# PID_controller.net
KiCad netlist of a schematic drawn in Altium Designer
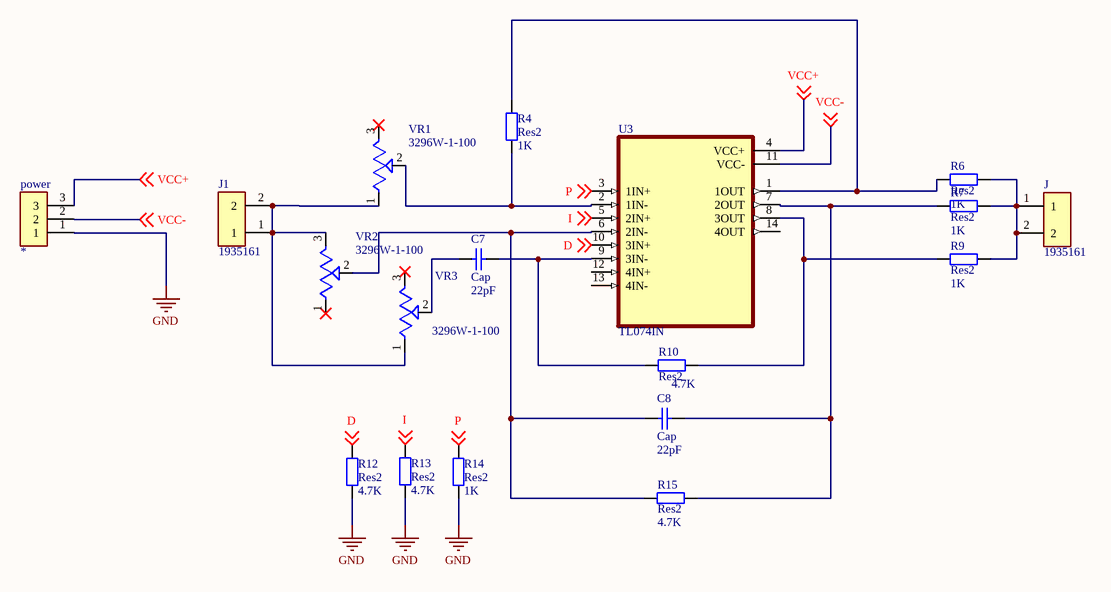
[diagram p0: PID_controller.SchDoc]

(export (version "E")
  (design (tool "Eeschema 10.0.6"))
  (components
    (comp (ref "C7")
      (value "Cap")
      (footprint "RAD-0.3")
      (description "Capacitor")
      (fields (field (name "ALTIUM_VALUE") "22pF") (field (name "PUBLISHER") "Altium Limited"))
      (libsource (lib "Miscellaneous Devices") (part "Cap"))
    )
    (comp (ref "C8")
      (value "Cap")
      (footprint "RAD-0.3")
      (description "Capacitor")
      (fields (field (name "ALTIUM_VALUE") "22pF") (field (name "PUBLISHER") "Altium Limited"))
      (libsource (lib "Miscellaneous Devices") (part "Cap"))
    )
    (comp (ref "J")
      (value "1935161")
      (footprint "PHOENIX_1935161")
      (description "2 Position Wire to Board Terminal Block Horizontal with Board 0.197 _5.00mm_ Through Hole")
      (fields (field (name "MF") "Phoenix Contact") (field (name "DIGI-KEY_PART_NUMBER") "277-1667-ND"))
      (libsource (lib "") (part "1935161_1"))
    )
    (comp (ref "J1")
      (value "1935161")
      (footprint "PHOENIX_1935161")
      (description "2 Position Wire to Board Terminal Block Horizontal with Board 0.197 _5.00mm_ Through Hole")
      (fields (field (name "MF") "Phoenix Contact") (field (name "DIGI-KEY_PART_NUMBER") "277-1667-ND"))
      (libsource (lib "1935161 (1)") (part "1935161"))
    )
    (comp (ref "power")
      (value "282837-3")
      (footprint "TE_282837-3")
      (description "Wire to Board 3 Position 5.08 mm Pitch 30-16 AWG Euro Style Terminal Block")
      (fields
        (field (name "MF") "TE Connectivity")
        (field (name "DIGI-KEY_PART_NUMBER") "A113321-ND")
        (field (name "COMMENT_1") "*")
      )
      (libsource (lib "282837-3") (part "282837-3"))
    )
    (comp (ref "R4")
      (value "Res2")
      (footprint "AXIAL-0.4")
      (description "Resistor")
      (fields (field (name "ALTIUM_VALUE") "1K") (field (name "PUBLISHER") "Altium Limited"))
      (libsource (lib "") (part "Res2_2"))
    )
    (comp (ref "R6")
      (value "Res2")
      (footprint "AXIAL-0.4")
      (description "Resistor")
      (fields (field (name "ALTIUM_VALUE") "1K") (field (name "PUBLISHER") "Altium Limited"))
      (libsource (lib "Miscellaneous Devices") (part "Res2"))
    )
    (comp (ref "R7")
      (value "Res2")
      (footprint "AXIAL-0.4")
      (description "Resistor")
      (fields (field (name "ALTIUM_VALUE") "1K") (field (name "PUBLISHER") "Altium Limited"))
      (libsource (lib "Miscellaneous Devices") (part "Res2"))
    )
    (comp (ref "R9")
      (value "Res2")
      (footprint "AXIAL-0.4")
      (description "Resistor")
      (fields (field (name "ALTIUM_VALUE") "1K") (field (name "PUBLISHER") "Altium Limited"))
      (libsource (lib "Miscellaneous Devices") (part "Res2"))
    )
    (comp (ref "R10")
      (value "Res2")
      (footprint "AXIAL-0.4")
      (description "Resistor")
      (fields (field (name "ALTIUM_VALUE") "4.7K") (field (name "PUBLISHER") "Altium Limited"))
      (libsource (lib "Miscellaneous Devices") (part "Res2"))
    )
    (comp (ref "R12")
      (value "Res2")
      (footprint "AXIAL-0.4")
      (description "Resistor")
      (fields (field (name "ALTIUM_VALUE") "4.7K") (field (name "PUBLISHER") "Altium Limited"))
      (libsource (lib "") (part "Res2_2"))
    )
    (comp (ref "R13")
      (value "Res2")
      (footprint "AXIAL-0.4")
      (description "Resistor")
      (fields (field (name "ALTIUM_VALUE") "4.7K") (field (name "PUBLISHER") "Altium Limited"))
      (libsource (lib "") (part "Res2_2"))
    )
    (comp (ref "R14")
      (value "Res2")
      (footprint "AXIAL-0.4")
      (description "Resistor")
      (fields (field (name "ALTIUM_VALUE") "1K") (field (name "PUBLISHER") "Altium Limited"))
      (libsource (lib "") (part "Res2_2"))
    )
    (comp (ref "R15")
      (value "Res2")
      (footprint "AXIAL-0.4")
      (description "Resistor")
      (fields (field (name "ALTIUM_VALUE") "4.7K") (field (name "PUBLISHER") "Altium Limited"))
      (libsource (lib "") (part "Res2_1"))
    )
    (comp (ref "U3")
      (value "TL074IN")
      (footprint "DIP794W45P254L1969H508Q14")
      (description "J-FET Amplifier 4 Circuit 14-DIP")
      (fields (field (name "MF") "STMicroelectronics"))
      (libsource (lib "TL074IN") (part "TL074IN"))
    )
    (comp (ref "VR1")
      (value "3296W-1-100")
      (footprint "TRIM_3296W-1-100")
      (description "10 Ohms 0.5W, 1/2W PC Pins Through Hole Trimmer Potentiometer Cermet 25 Turn Top Adjustment")
      (fields (field (name "MF") "Bourns") (field (name "DIGI-KEY_PART_NUMBER") "3296W-100LF-ND"))
      (libsource (lib "3296W-1-100") (part "3296W-1-100"))
    )
    (comp (ref "VR2")
      (value "3296W-1-100")
      (footprint "TRIM_3296W-1-100")
      (description "10 Ohms 0.5W, 1/2W PC Pins Through Hole Trimmer Potentiometer Cermet 25 Turn Top Adjustment")
      (fields (field (name "MF") "Bourns") (field (name "DIGI-KEY_PART_NUMBER") "3296W-100LF-ND"))
      (libsource (lib "3296W-1-100") (part "3296W-1-100"))
    )
    (comp (ref "VR3")
      (value "3296W-1-100")
      (footprint "TRIM_3296W-1-100")
      (description "10 Ohms 0.5W, 1/2W PC Pins Through Hole Trimmer Potentiometer Cermet 25 Turn Top Adjustment")
      (fields (field (name "MF") "Bourns") (field (name "DIGI-KEY_PART_NUMBER") "3296W-100LF-ND"))
      (libsource (lib "3296W-1-100") (part "3296W-1-100"))
    )
  )
  (nets
    (net (code "1") (name "D") (class "Default")
      (node (ref "R12") (pin "2") (pinfunction "2_2") (pintype "passive"))
      (node (ref "U3") (pin "10") (pinfunction "3IN+_10") (pintype "input"))
    )
    (net (code "2") (name "GND") (class "Default")
      (node (ref "R12") (pin "1") (pinfunction "1_1") (pintype "passive"))
      (node (ref "R13") (pin "1") (pinfunction "1_1") (pintype "passive"))
      (node (ref "R14") (pin "1") (pinfunction "1_1") (pintype "passive"))
      (node (ref "power") (pin "1") (pinfunction "1_1") (pintype "passive"))
    )
    (net (code "3") (name "I") (class "Default")
      (node (ref "R13") (pin "2") (pinfunction "2_2") (pintype "passive"))
      (node (ref "U3") (pin "5") (pinfunction "2IN+_5") (pintype "input"))
    )
    (net (code "4") (name "Net-(J-Pad1)") (class "Default")
      (node (ref "J") (pin "1") (pinfunction "1_1") (pintype "passive"))
      (node (ref "J") (pin "2") (pinfunction "2_2") (pintype "passive"))
      (node (ref "R6") (pin "2") (pinfunction "2_2") (pintype "passive"))
      (node (ref "R7") (pin "2") (pinfunction "2_2") (pintype "passive"))
      (node (ref "R9") (pin "2") (pinfunction "2_2") (pintype "passive"))
    )
    (net (code "5") (name "Net-(U3-1IN-)") (class "Default")
      (node (ref "R4") (pin "1") (pinfunction "1_1") (pintype "passive"))
      (node (ref "U3") (pin "2") (pinfunction "1IN-_2") (pintype "input"))
      (node (ref "VR1") (pin "2") (pinfunction "WIPER_2") (pintype "passive"))
    )
    (net (code "6") (name "Net-(U3-1OUT)") (class "Default")
      (node (ref "R4") (pin "2") (pinfunction "2_2") (pintype "passive"))
      (node (ref "R6") (pin "1") (pinfunction "1_1") (pintype "passive"))
      (node (ref "U3") (pin "1") (pinfunction "1OUT_1") (pintype "output"))
    )
    (net (code "7") (name "Net-(U3-2IN-)") (class "Default")
      (node (ref "C8") (pin "1") (pinfunction "1_1") (pintype "passive"))
      (node (ref "R15") (pin "2") (pinfunction "2_2") (pintype "passive"))
      (node (ref "U3") (pin "6") (pinfunction "2IN-_6") (pintype "input"))
      (node (ref "VR2") (pin "2") (pinfunction "WIPER_2") (pintype "passive"))
    )
    (net (code "8") (name "Net-(U3-2OUT)") (class "Default")
      (node (ref "C8") (pin "2") (pinfunction "2_2") (pintype "passive"))
      (node (ref "R15") (pin "1") (pinfunction "1_1") (pintype "passive"))
      (node (ref "R7") (pin "1") (pinfunction "1_1") (pintype "passive"))
      (node (ref "U3") (pin "7") (pinfunction "2OUT_7") (pintype "output"))
    )
    (net (code "9") (name "Net-(U3-3IN-)") (class "Default")
      (node (ref "C7") (pin "2") (pinfunction "2_2") (pintype "passive"))
      (node (ref "R10") (pin "1") (pinfunction "1_1") (pintype "passive"))
      (node (ref "U3") (pin "9") (pinfunction "3IN-_9") (pintype "input"))
    )
    (net (code "10") (name "Net-(U3-3OUT)") (class "Default")
      (node (ref "R10") (pin "2") (pinfunction "2_2") (pintype "passive"))
      (node (ref "R9") (pin "1") (pinfunction "1_1") (pintype "passive"))
      (node (ref "U3") (pin "8") (pinfunction "3OUT_8") (pintype "output"))
    )
    (net (code "11") (name "Net-(VR1-CCW)") (class "Default")
      (node (ref "J1") (pin "1") (pinfunction "1_1") (pintype "passive"))
      (node (ref "J1") (pin "2") (pinfunction "2_2") (pintype "passive"))
      (node (ref "VR1") (pin "1") (pinfunction "CCW_1") (pintype "passive"))
      (node (ref "VR2") (pin "3") (pinfunction "CW_3") (pintype "passive"))
      (node (ref "VR3") (pin "1") (pinfunction "CCW_1") (pintype "passive"))
    )
    (net (code "12") (name "Net-(VR3-WIPER)") (class "Default")
      (node (ref "C7") (pin "1") (pinfunction "1_1") (pintype "passive"))
      (node (ref "VR3") (pin "2") (pinfunction "WIPER_2") (pintype "passive"))
    )
    (net (code "13") (name "P") (class "Default")
      (node (ref "R14") (pin "2") (pinfunction "2_2") (pintype "passive"))
      (node (ref "U3") (pin "3") (pinfunction "1IN+_3") (pintype "input"))
    )
    (net (code "14") (name "VCC+") (class "Default")
      (node (ref "U3") (pin "4") (pinfunction "VCC+_4") (pintype "power_in"))
      (node (ref "power") (pin "3") (pinfunction "3_3") (pintype "passive"))
    )
    (net (code "15") (name "VCC-") (class "Default")
      (node (ref "U3") (pin "11") (pinfunction "VCC-_11") (pintype "power_in"))
      (node (ref "power") (pin "2") (pinfunction "2_2") (pintype "passive"))
    )
    (net (code "16") (name "unconnected-(U3-4IN+-Pad12)") (class "Default")
      (node (ref "U3") (pin "12") (pinfunction "4IN+_12") (pintype "input"))
    )
    (net (code "17") (name "unconnected-(U3-4IN--Pad13)") (class "Default")
      (node (ref "U3") (pin "13") (pinfunction "4IN-_13") (pintype "input"))
    )
    (net (code "18") (name "unconnected-(U3-4OUT-Pad14)") (class "Default")
      (node (ref "U3") (pin "14") (pinfunction "4OUT_14") (pintype "output"))
    )
    (net (code "19") (name "unconnected-(VR1-CW-Pad3)") (class "Default")
      (node (ref "VR1") (pin "3") (pinfunction "CW_3") (pintype "passive+no_connect"))
    )
    (net (code "20") (name "unconnected-(VR2-CCW-Pad1)") (class "Default")
      (node (ref "VR2") (pin "1") (pinfunction "CCW_1") (pintype "passive+no_connect"))
    )
    (net (code "21") (name "unconnected-(VR3-CW-Pad3)") (class "Default")
      (node (ref "VR3") (pin "3") (pinfunction "CW_3") (pintype "passive+no_connect"))
    )
  )
)
